# RLC_filter.net
KiCad netlist of a schematic drawn in Altium Designer
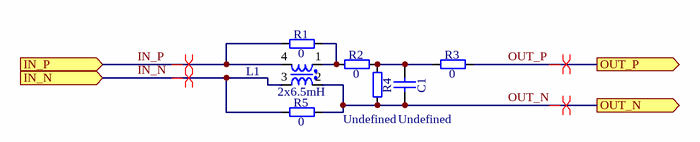
[diagram p0: RLC_filter.SchDoc]

(export (version "E")
  (design (tool "Eeschema 10.0.6"))
  (components
    (comp (ref "C1")
      (value "Undefined")
      (footprint "CAPC2012X135N")
      (description "Non-polarised capacitor")
      (fields (field (name "PART NUMBER") "CC0805_NO-VALUE") (field (name "AUTHOR") "CERN DEM JLC"))
      (libsource (lib "Capacitors") (part "Capacitor - non polarized"))
    )
    (comp (ref "L1")
      (value "2x6.5mH")
      (footprint "IND_WURTH_WE-SL2")
      (description "Inductor Common Mode")
      (fields
        (field (name "PART NUMBER") "IND_6.5MH_50%_WURTH_WE-SL2-744229")
        (field (name "POWER") "400mA")
        (field (name "AUTHOR") "CERN DEM JLC")
      )
      (libsource (lib "Inductors & Transformers") (part "Inductor Common Mode 1Dot-4 2Dot-3"))
    )
    (comp (ref "R1")
      (value "0")
      (footprint "RESC1608X55N")
      (description "Resistor")
      (fields
        (field (name "PART NUMBER") "R0603_0R_JUMPER")
        (field (name "MANUFACTURER") "GENERIC")
        (field (name "AUTHOR") "CERN DEM JLC")
      )
      (libsource (lib "Resistors") (part "Resistor"))
    )
    (comp (ref "R2")
      (value "0")
      (footprint "RESC1608X55N")
      (description "Resistor")
      (fields
        (field (name "PART NUMBER") "R0603_0R_JUMPER")
        (field (name "MANUFACTURER") "GENERIC")
        (field (name "AUTHOR") "CERN DEM JLC")
      )
      (libsource (lib "Resistors") (part "Resistor"))
    )
    (comp (ref "R3")
      (value "0")
      (footprint "RESC1608X55N")
      (description "Resistor")
      (fields
        (field (name "PART NUMBER") "R0603_0R_JUMPER")
        (field (name "MANUFACTURER") "GENERIC")
        (field (name "AUTHOR") "CERN DEM JLC")
      )
      (libsource (lib "Resistors") (part "Resistor"))
    )
    (comp (ref "R4")
      (value "Undefined")
      (footprint "RESC1608X55N")
      (description "Resistor")
      (fields (field (name "PART NUMBER") "R0603_NO-VALUE") (field (name "AUTHOR") "CERN DEM JLC"))
      (libsource (lib "Resistors") (part "Resistor"))
    )
    (comp (ref "R5")
      (value "0")
      (footprint "RESC1608X55N")
      (description "Resistor")
      (fields
        (field (name "PART NUMBER") "R0603_0R_JUMPER")
        (field (name "MANUFACTURER") "GENERIC")
        (field (name "AUTHOR") "CERN DEM JLC")
      )
      (libsource (lib "Resistors") (part "Resistor"))
    )
  )
  (nets
    (net (code "1") (name "/IN_N") (class "Default")
      (node (ref "L1") (pin "3") (pinfunction "3_3") (pintype "passive"))
      (node (ref "R5") (pin "2") (pinfunction "2_2") (pintype "passive"))
    )
    (net (code "2") (name "/IN_P") (class "Default")
      (node (ref "L1") (pin "4") (pinfunction "4_4") (pintype "passive"))
      (node (ref "R1") (pin "2") (pinfunction "2_2") (pintype "passive"))
    )
    (net (code "3") (name "/OUT_N") (class "Default")
      (node (ref "C1") (pin "1") (pinfunction "1_1") (pintype "passive"))
      (node (ref "L1") (pin "2") (pinfunction "2_2") (pintype "passive"))
      (node (ref "R4") (pin "1") (pinfunction "1_1") (pintype "passive"))
      (node (ref "R5") (pin "1") (pinfunction "1_1") (pintype "passive"))
    )
    (net (code "4") (name "/OUT_P") (class "Default")
      (node (ref "R3") (pin "1") (pinfunction "1_1") (pintype "passive"))
    )
    (net (code "5") (name "Net-(C1-Pad2)") (class "Default")
      (node (ref "C1") (pin "2") (pinfunction "2_2") (pintype "passive"))
      (node (ref "R2") (pin "1") (pinfunction "1_1") (pintype "passive"))
      (node (ref "R3") (pin "2") (pinfunction "2_2") (pintype "passive"))
      (node (ref "R4") (pin "2") (pinfunction "2_2") (pintype "passive"))
    )
    (net (code "6") (name "Net-(L1-Pad1)") (class "Default")
      (node (ref "L1") (pin "1") (pinfunction "1_1") (pintype "passive"))
      (node (ref "R1") (pin "1") (pinfunction "1_1") (pintype "passive"))
      (node (ref "R2") (pin "2") (pinfunction "2_2") (pintype "passive"))
    )
  )
)
